# trinamic-controller-dribbler.net
KiCad netlist of a schematic drawn in Altium Designer
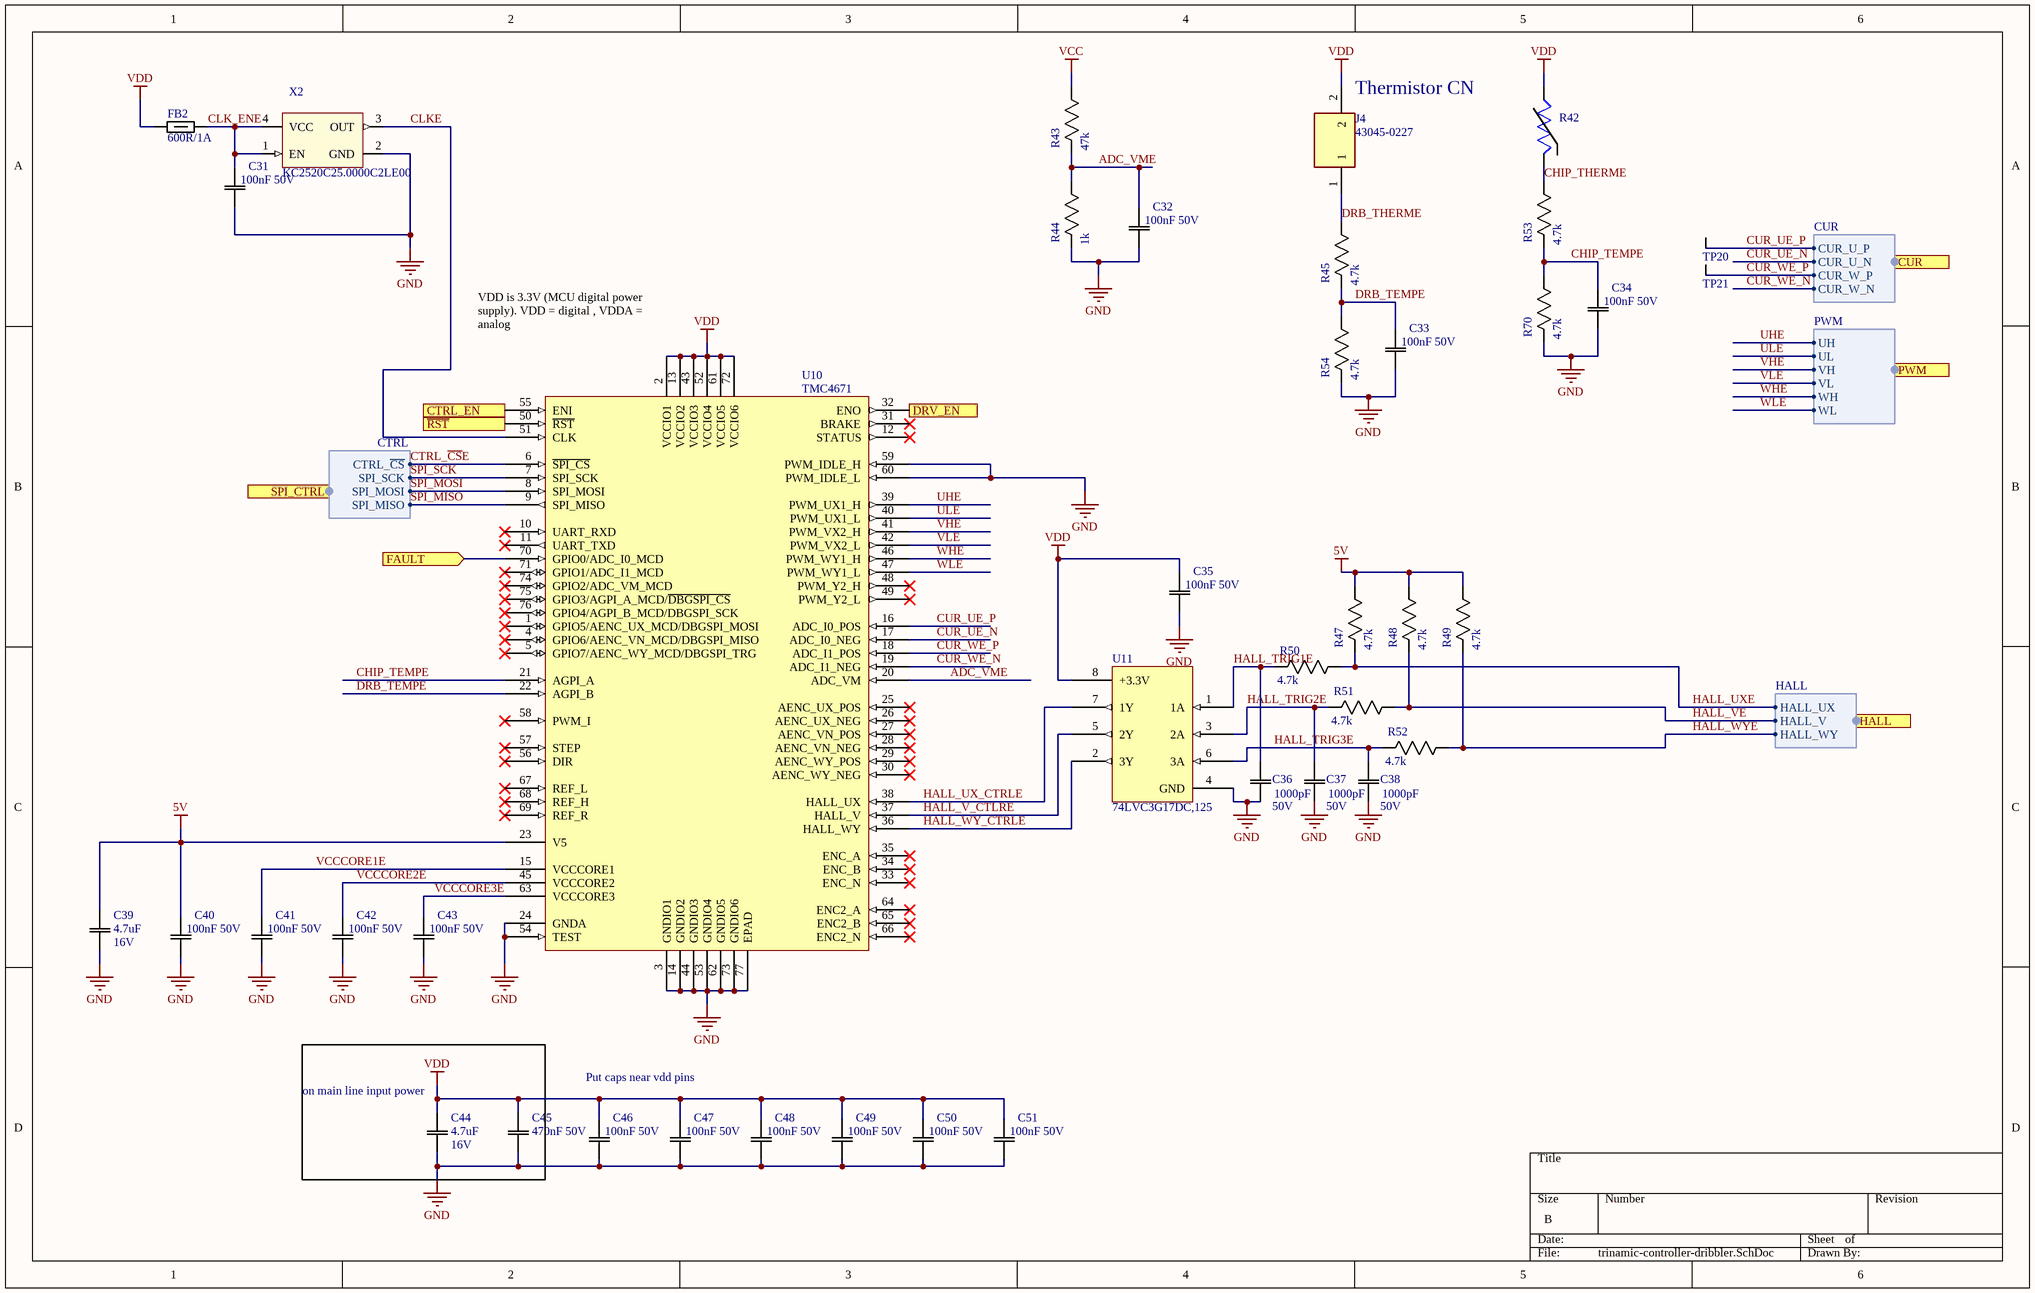
[diagram p0: trinamic-controller-dribbler.SchDoc]

(export (version "E")
  (design (tool "Eeschema 10.0.6"))
  (components
    (comp (ref "C31")
      (value "100nF 50V")
      (footprint "0603")
      (description "Default Symbol for Capacitors")
      (fields (field (name "TOLERANCE") "10%") (field (name "PART NUMBER") "CAP 100nF 50V"))
      (libsource (lib "capacitor_library") (part "CAP_Default"))
    )
    (comp (ref "C32")
      (value "100nF 50V")
      (footprint "0603")
      (description "Default Symbol for Capacitors")
      (fields (field (name "TOLERANCE") "10%") (field (name "PART NUMBER") "CAP 100nF 50V"))
      (libsource (lib "capacitor_library") (part "CAP_Default"))
    )
    (comp (ref "C33")
      (value "100nF 50V")
      (footprint "0603")
      (description "Default Symbol for Capacitors")
      (fields (field (name "TOLERANCE") "10%") (field (name "PART NUMBER") "CAP 100nF 50V"))
      (libsource (lib "capacitor_library") (part "CAP_Default"))
    )
    (comp (ref "C34")
      (value "100nF 50V")
      (footprint "0603")
      (description "Default Symbol for Capacitors")
      (fields (field (name "TOLERANCE") "10%") (field (name "PART NUMBER") "CAP 100nF 50V"))
      (libsource (lib "capacitor_library") (part "CAP_Default"))
    )
    (comp (ref "C35")
      (value "100nF 50V")
      (footprint "0603")
      (description "Default Symbol for Capacitors")
      (fields (field (name "TOLERANCE") "10%") (field (name "PART NUMBER") "CAP 100nF 50V"))
      (libsource (lib "capacitor_library") (part "CAP_Default"))
    )
    (comp (ref "C36")
      (value "1000pF")
      (footprint "0603")
      (description "Default Symbol for Capacitors")
      (fields
        (field (name "TOLERANCE") "10%")
        (field (name "RATING") "50V")
        (field (name "PART NUMBER") "CAP 1000pF 50V")
      )
      (libsource (lib "capacitor_library") (part "CAP_Default"))
    )
    (comp (ref "C37")
      (value "1000pF")
      (footprint "0603")
      (description "Default Symbol for Capacitors")
      (fields
        (field (name "TOLERANCE") "10%")
        (field (name "RATING") "50V")
        (field (name "PART NUMBER") "CAP 1000pF 50V")
      )
      (libsource (lib "capacitor_library") (part "CAP_Default"))
    )
    (comp (ref "C38")
      (value "1000pF")
      (footprint "0603")
      (description "Default Symbol for Capacitors")
      (fields
        (field (name "TOLERANCE") "10%")
        (field (name "RATING") "50V")
        (field (name "PART NUMBER") "CAP 1000pF 50V")
      )
      (libsource (lib "capacitor_library") (part "CAP_Default"))
    )
    (comp (ref "C39")
      (value "4.7uF")
      (footprint "0603")
      (description "Default Symbol for Capacitors")
      (fields
        (field (name "TOLERANCE") "10%")
        (field (name "RATING") "16V")
        (field (name "PART NUMBER") "CAP 4.7uF 16V")
      )
      (libsource (lib "capacitor_library") (part "CAP_Default"))
    )
    (comp (ref "C40")
      (value "100nF 50V")
      (footprint "0603")
      (description "Default Symbol for Capacitors")
      (fields (field (name "TOLERANCE") "10%") (field (name "PART NUMBER") "CAP 100nF 50V"))
      (libsource (lib "capacitor_library") (part "CAP_Default"))
    )
    (comp (ref "C41")
      (value "100nF 50V")
      (footprint "0603")
      (description "Default Symbol for Capacitors")
      (fields (field (name "TOLERANCE") "10%") (field (name "PART NUMBER") "CAP 100nF 50V"))
      (libsource (lib "capacitor_library") (part "CAP_Default"))
    )
    (comp (ref "C42")
      (value "100nF 50V")
      (footprint "0603")
      (description "Default Symbol for Capacitors")
      (fields (field (name "TOLERANCE") "10%") (field (name "PART NUMBER") "CAP 100nF 50V"))
      (libsource (lib "capacitor_library") (part "CAP_Default"))
    )
    (comp (ref "C43")
      (value "100nF 50V")
      (footprint "0603")
      (description "Default Symbol for Capacitors")
      (fields (field (name "TOLERANCE") "10%") (field (name "PART NUMBER") "CAP 100nF 50V"))
      (libsource (lib "capacitor_library") (part "CAP_Default"))
    )
    (comp (ref "C44")
      (value "4.7uF")
      (footprint "0603")
      (description "Default Symbol for Capacitors")
      (fields
        (field (name "TOLERANCE") "10%")
        (field (name "RATING") "16V")
        (field (name "PART NUMBER") "CAP 4.7uF 16V")
      )
      (libsource (lib "capacitor_library") (part "CAP_Default"))
    )
    (comp (ref "C45")
      (value "470nF 50V")
      (footprint "0603")
      (description "Default Symbol for Capacitors")
      (fields (field (name "TOLERANCE") "10%") (field (name "PART NUMBER") "CAP 470nF 50V"))
      (libsource (lib "capacitor_library") (part "CAP_Default"))
    )
    (comp (ref "C46")
      (value "100nF 50V")
      (footprint "0603")
      (description "Default Symbol for Capacitors")
      (fields (field (name "TOLERANCE") "10%") (field (name "PART NUMBER") "CAP 100nF 50V"))
      (libsource (lib "capacitor_library") (part "CAP_Default"))
    )
    (comp (ref "C47")
      (value "100nF 50V")
      (footprint "0603")
      (description "Default Symbol for Capacitors")
      (fields (field (name "TOLERANCE") "10%") (field (name "PART NUMBER") "CAP 100nF 50V"))
      (libsource (lib "capacitor_library") (part "CAP_Default"))
    )
    (comp (ref "C48")
      (value "100nF 50V")
      (footprint "0603")
      (description "Default Symbol for Capacitors")
      (fields (field (name "TOLERANCE") "10%") (field (name "PART NUMBER") "CAP 100nF 50V"))
      (libsource (lib "capacitor_library") (part "CAP_Default"))
    )
    (comp (ref "C49")
      (value "100nF 50V")
      (footprint "0603")
      (description "Default Symbol for Capacitors")
      (fields (field (name "TOLERANCE") "10%") (field (name "PART NUMBER") "CAP 100nF 50V"))
      (libsource (lib "capacitor_library") (part "CAP_Default"))
    )
    (comp (ref "C50")
      (value "100nF 50V")
      (footprint "0603")
      (description "Default Symbol for Capacitors")
      (fields (field (name "TOLERANCE") "10%") (field (name "PART NUMBER") "CAP 100nF 50V"))
      (libsource (lib "capacitor_library") (part "CAP_Default"))
    )
    (comp (ref "C51")
      (value "100nF 50V")
      (footprint "0603")
      (description "Default Symbol for Capacitors")
      (fields (field (name "TOLERANCE") "10%") (field (name "PART NUMBER") "CAP 100nF 50V"))
      (libsource (lib "capacitor_library") (part "CAP_Default"))
    )
    (comp (ref "FB2")
      (value "600R/1A")
      (footprint "0603")
      (fields (field (name "PART NUMBER") "FERRITE BEAD 200 MOHM 0603 1LN"))
      (libsource (lib "Inductor_Library") (part "FERRITE BEAD 200 MOHM 0603 1LN"))
    )
    (comp (ref "J4")
      (value "43045-0227")
      (footprint "MOLEX_0430450227")
      (description "Molex 43045-0227 2POS Microfit\r\ndual row, Vertical")
      (fields (field (name "PART NUMBER") "CN HDR 2POS Molex 43045-0227"))
      (libsource (lib "Connector_Library") (part "CN HDR 2POS Molex 43045-0227"))
    )
    (comp (ref "R42")
      (value "RES NTC 10k")
      (footprint "0603")
      (fields (field (name "PART NUMBER") "RES NTC 10k CHIP") (field (name "TOLERANCE") "1%"))
      (libsource (lib "Resistor_Library") (part "RES NTC 10k"))
    )
    (comp (ref "R43")
      (value "47k")
      (footprint "0603")
      (description "Default Resistor Symbol")
      (fields (field (name "TOLERANCE") "1%") (field (name "PART NUMBER") "RES 47k 1/8W - 1%"))
      (libsource (lib "") (part "RES_DEFAULT_2"))
    )
    (comp (ref "R44")
      (value "1k")
      (footprint "0603")
      (description "Default Resistor Symbol")
      (fields (field (name "TOLERANCE") "1%") (field (name "PART NUMBER") "RES 1k 1/8W - 1%"))
      (libsource (lib "") (part "RES_DEFAULT_1"))
    )
    (comp (ref "R45")
      (value "4.7k")
      (footprint "0603")
      (description "Default Resistor Symbol")
      (fields (field (name "TOLERANCE") "1%") (field (name "PART NUMBER") "RES 4.7k 1/8W - 1%"))
      (libsource (lib "") (part "RES_DEFAULT_1"))
    )
    (comp (ref "R47")
      (value "4.7k")
      (footprint "0603")
      (description "Default Resistor Symbol")
      (fields (field (name "TOLERANCE") "5%") (field (name "PART NUMBER") "RES 4.7k 1/8W - 5%"))
      (libsource (lib "Resistor_Library") (part "RES_DEFAULT"))
    )
    (comp (ref "R48")
      (value "4.7k")
      (footprint "0603")
      (description "Default Resistor Symbol")
      (fields (field (name "TOLERANCE") "5%") (field (name "PART NUMBER") "RES 4.7k 1/8W - 5%"))
      (libsource (lib "Resistor_Library") (part "RES_DEFAULT"))
    )
    (comp (ref "R49")
      (value "4.7k")
      (footprint "0603")
      (description "Default Resistor Symbol")
      (fields (field (name "TOLERANCE") "5%") (field (name "PART NUMBER") "RES 4.7k 1/8W - 5%"))
      (libsource (lib "") (part "RES_DEFAULT_1"))
    )
    (comp (ref "R50")
      (value "4.7k")
      (footprint "0603")
      (description "Default Resistor Symbol")
      (fields (field (name "TOLERANCE") "5%") (field (name "PART NUMBER") "RES 4.7k 1/8W - 5%"))
      (libsource (lib "Resistor_Library") (part "RES_DEFAULT"))
    )
    (comp (ref "R51")
      (value "4.7k")
      (footprint "0603")
      (description "Default Resistor Symbol")
      (fields (field (name "TOLERANCE") "5%") (field (name "PART NUMBER") "RES 4.7k 1/8W - 5%"))
      (libsource (lib "Resistor_Library") (part "RES_DEFAULT"))
    )
    (comp (ref "R52")
      (value "4.7k")
      (footprint "0603")
      (description "Default Resistor Symbol")
      (fields (field (name "TOLERANCE") "5%") (field (name "PART NUMBER") "RES 4.7k 1/8W - 5%"))
      (libsource (lib "Resistor_Library") (part "RES_DEFAULT"))
    )
    (comp (ref "R53")
      (value "4.7k")
      (footprint "0603")
      (description "Default Resistor Symbol")
      (fields (field (name "TOLERANCE") "1%") (field (name "PART NUMBER") "RES 4.7k 1/8W - 1%"))
      (libsource (lib "") (part "RES_DEFAULT_1"))
    )
    (comp (ref "R54")
      (value "4.7k")
      (footprint "0603")
      (description "Default Resistor Symbol")
      (fields (field (name "TOLERANCE") "1%") (field (name "PART NUMBER") "RES 4.7k 1/8W - 1%"))
      (libsource (lib "") (part "RES_DEFAULT_1"))
    )
    (comp (ref "R70")
      (value "4.7k")
      (footprint "0603")
      (description "Default Resistor Symbol")
      (fields (field (name "TOLERANCE") "1%") (field (name "PART NUMBER") "RES 4.7k 1/8W - 1%"))
      (libsource (lib "") (part "RES_DEFAULT_1"))
    )
    (comp (ref "TP20")
      (value "C_UE")
      (footprint "TP")
      (fields (field (name "PART NUMBER") "Test Point (Via)"))
      (libsource (lib "IC_Library") (part "Test Point (Via)"))
    )
    (comp (ref "TP21")
      (value "C_WE")
      (footprint "TP")
      (fields (field (name "PART NUMBER") "Test Point (Via)"))
      (libsource (lib "IC_Library") (part "Test Point (Via)"))
    )
    (comp (ref "U10")
      (value "TMC4671")
      (footprint "QFN40P1050X650X90_HS-77N")
      (description "Motor Driver, -40 To 125Deg C Rohs Compliant: Yes")
      (libsource (lib "IC_Library") (part "TMC4671"))
    )
    (comp (ref "U11")
      (value "74LVC3G17DC,125")
      (footprint "8-VSSOP")
      (description "IC BUFFER TRIPLE SCHMITT TRIGGER 5.5V VSSOP-8")
      (fields (field (name "PART NUMBER") "IC 74LVC3G17DC,125"))
      (libsource (lib "IC_Library") (part "IC 74LVC3G17DC,125"))
    )
    (comp (ref "X2")
      (value "KC2520C25.0000C2LE00")
      (footprint "KC2520C25.0000C2LE00")
      (description "Oscillator XO 25MHz ±15ppm 15pF CMOS 55% 2.5V/3.3V 4-Pin Mini-CSMD T/R")
      (fields (field (name "PART NUMBER") "XTAL OSC 25MHz 3.3V"))
      (libsource (lib "Oscillator_Library") (part "XTAL OSC 25MHz 3.3V"))
    )
  )
  (nets
    (net (code "5") (name "/ADC_VME") (class "Default")
      (node (ref "C32") (pin "2") (pinfunction "C2_2") (pintype "passive"))
      (node (ref "R43") (pin "2") (pinfunction "R2_2") (pintype "passive"))
      (node (ref "R44") (pin "1") (pinfunction "R1_1") (pintype "passive"))
      (node (ref "U10") (pin "20") (pinfunction "ADC_VM_20") (pintype "input"))
    )
    (net (code "6") (name "/CHIP_TEMPE") (class "Default")
      (node (ref "C34") (pin "2") (pinfunction "C2_2") (pintype "passive"))
      (node (ref "R53") (pin "2") (pinfunction "R2_2") (pintype "passive"))
      (node (ref "R70") (pin "1") (pinfunction "R1_1") (pintype "passive"))
      (node (ref "U10") (pin "21") (pinfunction "AGPI_A_21") (pintype "input"))
    )
    (net (code "7") (name "/CHIP_THERME") (class "Default")
      (node (ref "R42") (pin "1") (pinfunction "1_1") (pintype "passive"))
      (node (ref "R53") (pin "1") (pinfunction "R1_1") (pintype "passive"))
    )
    (net (code "8") (name "/CLKE") (class "Default")
      (node (ref "U10") (pin "51") (pinfunction "CLK_51") (pintype "input"))
      (node (ref "X2") (pin "3") (pinfunction "OUT_3") (pintype "output"))
    )
    (net (code "9") (name "/CLK_ENE") (class "Default")
      (node (ref "C31") (pin "2") (pinfunction "C2_2") (pintype "passive"))
      (node (ref "FB2") (pin "2") (pinfunction "2_2") (pintype "passive"))
      (node (ref "X2") (pin "1") (pinfunction "EN_1") (pintype "input"))
      (node (ref "X2") (pin "4") (pinfunction "VCC_4") (pintype "power_in"))
    )
    (net (code "10") (name "/CTRL_EN") (class "Default")
      (node (ref "U10") (pin "55") (pinfunction "ENI_55") (pintype "input"))
    )
    (net (code "11") (name "/CTRL_~{CS}E") (class "Default")
      (node (ref "U10") (pin "6") (pinfunction "~{SPI_CS}_6") (pintype "input"))
    )
    (net (code "12") (name "/CUR_UE_N") (class "Default")
      (node (ref "U10") (pin "17") (pinfunction "ADC_I0_NEG_17") (pintype "input"))
    )
    (net (code "13") (name "/CUR_UE_P") (class "Default")
      (node (ref "TP20") (pin "1") (pinfunction "1_1") (pintype "passive"))
      (node (ref "U10") (pin "16") (pinfunction "ADC_I0_POS_16") (pintype "input"))
    )
    (net (code "14") (name "/CUR_WE_N") (class "Default")
      (node (ref "U10") (pin "19") (pinfunction "ADC_I1_NEG_19") (pintype "input"))
    )
    (net (code "15") (name "/CUR_WE_P") (class "Default")
      (node (ref "TP21") (pin "1") (pinfunction "1_1") (pintype "passive"))
      (node (ref "U10") (pin "18") (pinfunction "ADC_I1_POS_18") (pintype "input"))
    )
    (net (code "16") (name "/DRB_TEMPE") (class "Default")
      (node (ref "C33") (pin "2") (pinfunction "C2_2") (pintype "passive"))
      (node (ref "R45") (pin "2") (pinfunction "R2_2") (pintype "passive"))
      (node (ref "R54") (pin "1") (pinfunction "R1_1") (pintype "passive"))
      (node (ref "U10") (pin "22") (pinfunction "AGPI_B_22") (pintype "input"))
    )
    (net (code "17") (name "/DRB_THERME") (class "Default")
      (node (ref "J4") (pin "1") (pinfunction "1_1") (pintype "passive"))
      (node (ref "R45") (pin "1") (pinfunction "R1_1") (pintype "passive"))
    )
    (net (code "18") (name "/DRV_EN") (class "Default")
      (node (ref "U10") (pin "32") (pinfunction "ENO_32") (pintype "output"))
    )
    (net (code "19") (name "/FAULT") (class "Default")
      (node (ref "U10") (pin "70") (pinfunction "GPIO0/ADC_I0_MCD_70") (pintype "input"))
    )
    (net (code "20") (name "/HALL_TRIG1E") (class "Default")
      (node (ref "C36") (pin "2") (pinfunction "C2_2") (pintype "passive"))
      (node (ref "R50") (pin "2") (pinfunction "R2_2") (pintype "passive"))
      (node (ref "U11") (pin "1") (pinfunction "1A_1") (pintype "input"))
    )
    (net (code "21") (name "/HALL_TRIG2E") (class "Default")
      (node (ref "C37") (pin "2") (pinfunction "C2_2") (pintype "passive"))
      (node (ref "R51") (pin "2") (pinfunction "R2_2") (pintype "passive"))
      (node (ref "U11") (pin "3") (pinfunction "2A_3") (pintype "input"))
    )
    (net (code "22") (name "/HALL_TRIG3E") (class "Default")
      (node (ref "C38") (pin "2") (pinfunction "C2_2") (pintype "passive"))
      (node (ref "R52") (pin "2") (pinfunction "R2_2") (pintype "passive"))
      (node (ref "U11") (pin "6") (pinfunction "3A_6") (pintype "input"))
    )
    (net (code "23") (name "/HALL_UXE") (class "Default")
      (node (ref "R47") (pin "2") (pinfunction "R2_2") (pintype "passive"))
      (node (ref "R50") (pin "1") (pinfunction "R1_1") (pintype "passive"))
    )
    (net (code "24") (name "/HALL_UX_CTRLE") (class "Default")
      (node (ref "U10") (pin "38") (pinfunction "HALL_UX_38") (pintype "input"))
      (node (ref "U11") (pin "7") (pinfunction "1Y_7") (pintype "output"))
    )
    (net (code "25") (name "/HALL_VE") (class "Default")
      (node (ref "R48") (pin "2") (pinfunction "R2_2") (pintype "passive"))
      (node (ref "R51") (pin "1") (pinfunction "R1_1") (pintype "passive"))
    )
    (net (code "26") (name "/HALL_V_CTLRE") (class "Default")
      (node (ref "U10") (pin "37") (pinfunction "HALL_V_37") (pintype "input"))
      (node (ref "U11") (pin "5") (pinfunction "2Y_5") (pintype "output"))
    )
    (net (code "27") (name "/HALL_WYE") (class "Default")
      (node (ref "R49") (pin "2") (pinfunction "R2_2") (pintype "passive"))
      (node (ref "R52") (pin "1") (pinfunction "R1_1") (pintype "passive"))
    )
    (net (code "28") (name "/HALL_WY_CTRLE") (class "Default")
      (node (ref "U10") (pin "36") (pinfunction "HALL_WY_36") (pintype "input"))
      (node (ref "U11") (pin "2") (pinfunction "3Y_2") (pintype "output"))
    )
    (net (code "29") (name "/SPI_MISO") (class "Default")
      (node (ref "U10") (pin "9") (pinfunction "SPI_MISO_9") (pintype "output"))
    )
    (net (code "30") (name "/SPI_MOSI") (class "Default")
      (node (ref "U10") (pin "8") (pinfunction "SPI_MOSI_8") (pintype "input"))
    )
    (net (code "31") (name "/SPI_SCK") (class "Default")
      (node (ref "U10") (pin "7") (pinfunction "SPI_SCK_7") (pintype "input"))
    )
    (net (code "32") (name "/UHE") (class "Default")
      (node (ref "U10") (pin "39") (pinfunction "PWM_UX1_H_39") (pintype "output"))
    )
    (net (code "33") (name "/ULE") (class "Default")
      (node (ref "U10") (pin "40") (pinfunction "PWM_UX1_L_40") (pintype "output"))
    )
    (net (code "34") (name "/VCCCORE1E") (class "Default")
      (node (ref "C41") (pin "2") (pinfunction "C2_2") (pintype "passive"))
      (node (ref "U10") (pin "15") (pinfunction "VCCCORE1_15") (pintype "power_in"))
    )
    (net (code "35") (name "/VCCCORE2E") (class "Default")
      (node (ref "C42") (pin "2") (pinfunction "C2_2") (pintype "passive"))
      (node (ref "U10") (pin "45") (pinfunction "VCCCORE2_45") (pintype "power_in"))
    )
    (net (code "36") (name "/VCCCORE3E") (class "Default")
      (node (ref "C43") (pin "2") (pinfunction "C2_2") (pintype "passive"))
      (node (ref "U10") (pin "63") (pinfunction "VCCCORE3_63") (pintype "power_in"))
    )
    (net (code "37") (name "/VHE") (class "Default")
      (node (ref "U10") (pin "41") (pinfunction "PWM_VX2_H_41") (pintype "output"))
    )
    (net (code "38") (name "/VLE") (class "Default")
      (node (ref "U10") (pin "42") (pinfunction "PWM_VX2_L_42") (pintype "output"))
    )
    (net (code "39") (name "/WHE") (class "Default")
      (node (ref "U10") (pin "46") (pinfunction "PWM_WY1_H_46") (pintype "output"))
    )
    (net (code "40") (name "/WLE") (class "Default")
      (node (ref "U10") (pin "47") (pinfunction "PWM_WY1_L_47") (pintype "output"))
    )
    (net (code "45") (name "/~{RST}") (class "Default")
      (node (ref "U10") (pin "50") (pinfunction "~{RST}_50") (pintype "input"))
    )
    (net (code "46") (name "5V") (class "Default")
      (node (ref "C39") (pin "2") (pinfunction "C2_2") (pintype "passive"))
      (node (ref "C40") (pin "2") (pinfunction "C2_2") (pintype "passive"))
      (node (ref "R47") (pin "1") (pinfunction "R1_1") (pintype "passive"))
      (node (ref "R48") (pin "1") (pinfunction "R1_1") (pintype "passive"))
      (node (ref "R49") (pin "1") (pinfunction "R1_1") (pintype "passive"))
      (node (ref "U10") (pin "23") (pinfunction "V5_23") (pintype "power_in"))
    )
    (net (code "47") (name "GND") (class "Default")
      (node (ref "C31") (pin "1") (pinfunction "C1_1") (pintype "passive"))
      (node (ref "C32") (pin "1") (pinfunction "C1_1") (pintype "passive"))
      (node (ref "C33") (pin "1") (pinfunction "C1_1") (pintype "passive"))
      (node (ref "C34") (pin "1") (pinfunction "C1_1") (pintype "passive"))
      (node (ref "C35") (pin "1") (pinfunction "C1_1") (pintype "passive"))
      (node (ref "C36") (pin "1") (pinfunction "C1_1") (pintype "passive"))
      (node (ref "C37") (pin "1") (pinfunction "C1_1") (pintype "passive"))
      (node (ref "C38") (pin "1") (pinfunction "C1_1") (pintype "passive"))
      (node (ref "C39") (pin "1") (pinfunction "C1_1") (pintype "passive"))
      (node (ref "C40") (pin "1") (pinfunction "C1_1") (pintype "passive"))
      (node (ref "C41") (pin "1") (pinfunction "C1_1") (pintype "passive"))
      (node (ref "C42") (pin "1") (pinfunction "C1_1") (pintype "passive"))
      (node (ref "C43") (pin "1") (pinfunction "C1_1") (pintype "passive"))
      (node (ref "C44") (pin "1") (pinfunction "C1_1") (pintype "passive"))
      (node (ref "C45") (pin "1") (pinfunction "C1_1") (pintype "passive"))
      (node (ref "C46") (pin "1") (pinfunction "C1_1") (pintype "passive"))
      (node (ref "C47") (pin "1") (pinfunction "C1_1") (pintype "passive"))
      (node (ref "C48") (pin "1") (pinfunction "C1_1") (pintype "passive"))
      (node (ref "C49") (pin "1") (pinfunction "C1_1") (pintype "passive"))
      (node (ref "C50") (pin "1") (pinfunction "C1_1") (pintype "passive"))
      (node (ref "C51") (pin "1") (pinfunction "C1_1") (pintype "passive"))
      (node (ref "R44") (pin "2") (pinfunction "R2_2") (pintype "passive"))
      (node (ref "R54") (pin "2") (pinfunction "R2_2") (pintype "passive"))
      (node (ref "R70") (pin "2") (pinfunction "R2_2") (pintype "passive"))
      (node (ref "U10") (pin "14") (pinfunction "GNDIO2_14") (pintype "power_in"))
      (node (ref "U10") (pin "24") (pinfunction "GNDA_24") (pintype "power_in"))
      (node (ref "U10") (pin "3") (pinfunction "GNDIO1_3") (pintype "power_in"))
      (node (ref "U10") (pin "44") (pinfunction "GNDIO3_44") (pintype "power_in"))
      (node (ref "U10") (pin "53") (pinfunction "GNDIO4_53") (pintype "power_in"))
      (node (ref "U10") (pin "54") (pinfunction "TEST_54") (pintype "input"))
      (node (ref "U10") (pin "59") (pinfunction "PWM_IDLE_H_59") (pintype "input"))
      (node (ref "U10") (pin "60") (pinfunction "PWM_IDLE_L_60") (pintype "input"))
      (node (ref "U10") (pin "62") (pinfunction "GNDIO5_62") (pintype "power_in"))
      (node (ref "U10") (pin "73") (pinfunction "GNDIO6_73") (pintype "power_in"))
      (node (ref "U10") (pin "77") (pinfunction "EPAD_77") (pintype "passive"))
      (node (ref "U11") (pin "4") (pinfunction "GND_4") (pintype "power_in"))
      (node (ref "X2") (pin "2") (pinfunction "GND_2") (pintype "power_in"))
    )
    (net (code "48") (name "VCC") (class "Default")
      (node (ref "R43") (pin "1") (pinfunction "R1_1") (pintype "passive"))
    )
    (net (code "49") (name "VDD") (class "Default")
      (node (ref "C35") (pin "2") (pinfunction "C2_2") (pintype "passive"))
      (node (ref "C44") (pin "2") (pinfunction "C2_2") (pintype "passive"))
      (node (ref "C45") (pin "2") (pinfunction "C2_2") (pintype "passive"))
      (node (ref "C46") (pin "2") (pinfunction "C2_2") (pintype "passive"))
      (node (ref "C47") (pin "2") (pinfunction "C2_2") (pintype "passive"))
      (node (ref "C48") (pin "2") (pinfunction "C2_2") (pintype "passive"))
      (node (ref "C49") (pin "2") (pinfunction "C2_2") (pintype "passive"))
      (node (ref "C50") (pin "2") (pinfunction "C2_2") (pintype "passive"))
      (node (ref "C51") (pin "2") (pinfunction "C2_2") (pintype "passive"))
      (node (ref "FB2") (pin "1") (pinfunction "1_1") (pintype "passive"))
      (node (ref "J4") (pin "2") (pinfunction "2_2") (pintype "passive"))
      (node (ref "R42") (pin "2") (pinfunction "2_2") (pintype "passive"))
      (node (ref "U10") (pin "13") (pinfunction "VCCIO2_13") (pintype "power_in"))
      (node (ref "U10") (pin "2") (pinfunction "VCCIO1_2") (pintype "power_in"))
      (node (ref "U10") (pin "43") (pinfunction "VCCIO3_43") (pintype "power_in"))
      (node (ref "U10") (pin "52") (pinfunction "VCCIO4_52") (pintype "power_in"))
      (node (ref "U10") (pin "61") (pinfunction "VCCIO5_61") (pintype "power_in"))
      (node (ref "U10") (pin "72") (pinfunction "VCCIO6_72") (pintype "power_in"))
      (node (ref "U11") (pin "8") (pinfunction "+3.3V_8") (pintype "power_in"))
    )
    (net (code "50") (name "unconnected-(U10-AENC_UX_NEG-Pad26)") (class "Default")
      (node (ref "U10") (pin "26") (pinfunction "AENC_UX_NEG_26") (pintype "input+no_connect"))
    )
    (net (code "51") (name "unconnected-(U10-AENC_UX_POS-Pad25)") (class "Default")
      (node (ref "U10") (pin "25") (pinfunction "AENC_UX_POS_25") (pintype "input+no_connect"))
    )
    (net (code "52") (name "unconnected-(U10-AENC_VN_NEG-Pad28)") (class "Default")
      (node (ref "U10") (pin "28") (pinfunction "AENC_VN_NEG_28") (pintype "input+no_connect"))
    )
    (net (code "53") (name "unconnected-(U10-AENC_VN_POS-Pad27)") (class "Default")
      (node (ref "U10") (pin "27") (pinfunction "AENC_VN_POS_27") (pintype "input+no_connect"))
    )
    (net (code "54") (name "unconnected-(U10-AENC_WY_NEG-Pad30)") (class "Default")
      (node (ref "U10") (pin "30") (pinfunction "AENC_WY_NEG_30") (pintype "input+no_connect"))
    )
    (net (code "55") (name "unconnected-(U10-AENC_WY_POS-Pad29)") (class "Default")
      (node (ref "U10") (pin "29") (pinfunction "AENC_WY_POS_29") (pintype "input+no_connect"))
    )
    (net (code "56") (name "unconnected-(U10-BRAKE-Pad31)") (class "Default")
      (node (ref "U10") (pin "31") (pinfunction "BRAKE_31") (pintype "output+no_connect"))
    )
    (net (code "57") (name "unconnected-(U10-DIR-Pad56)") (class "Default")
      (node (ref "U10") (pin "56") (pinfunction "DIR_56") (pintype "input+no_connect"))
    )
    (net (code "58") (name "unconnected-(U10-ENC2_A-Pad64)") (class "Default")
      (node (ref "U10") (pin "64") (pinfunction "ENC2_A_64") (pintype "input+no_connect"))
    )
    (net (code "59") (name "unconnected-(U10-ENC2_B-Pad65)") (class "Default")
      (node (ref "U10") (pin "65") (pinfunction "ENC2_B_65") (pintype "input+no_connect"))
    )
    (net (code "60") (name "unconnected-(U10-ENC2_N-Pad66)") (class "Default")
      (node (ref "U10") (pin "66") (pinfunction "ENC2_N_66") (pintype "input+no_connect"))
    )
    (net (code "61") (name "unconnected-(U10-ENC_A-Pad35)") (class "Default")
      (node (ref "U10") (pin "35") (pinfunction "ENC_A_35") (pintype "input+no_connect"))
    )
    (net (code "62") (name "unconnected-(U10-ENC_B-Pad34)") (class "Default")
      (node (ref "U10") (pin "34") (pinfunction "ENC_B_34") (pintype "input+no_connect"))
    )
    (net (code "63") (name "unconnected-(U10-ENC_N-Pad33)") (class "Default")
      (node (ref "U10") (pin "33") (pinfunction "ENC_N_33") (pintype "input+no_connect"))
    )
    (net (code "64") (name "unconnected-(U10-GPIO1{slash}ADC_I1_MCD-Pad71)") (class "Default")
      (node (ref "U10") (pin "71") (pinfunction "GPIO1/ADC_I1_MCD_71") (pintype "bidirectional+no_connect"))
    )
    (net (code "65") (name "unconnected-(U10-GPIO2{slash}ADC_VM_MCD-Pad74)") (class "Default")
      (node (ref "U10") (pin "74") (pinfunction "GPIO2/ADC_VM_MCD_74") (pintype "bidirectional+no_connect"))
    )
    (net (code "66") (name "unconnected-(U10-GPIO3{slash}AGPI_A_MCD{slash}~{DBGSPI_CS}-Pad75)") (class "Default")
      (node (ref "U10") (pin "75") (pinfunction "GPIO3/AGPI_A_MCD/~{DBGSPI_CS}_75") (pintype "bidirectional+no_connect"))
    )
    (net (code "67") (name "unconnected-(U10-GPIO4{slash}AGPI_B_MCD{slash}DBGSPI_SCK-Pad76)") (class "Default")
      (node (ref "U10") (pin "76") (pinfunction "GPIO4/AGPI_B_MCD/DBGSPI_SCK_76") (pintype "bidirectional+no_connect"))
    )
    (net (code "68") (name "unconnected-(U10-GPIO5{slash}AENC_UX_MCD{slash}DBGSPI_MOSI-Pad1)") (class "Default")
      (node (ref "U10") (pin "1") (pinfunction "GPIO5/AENC_UX_MCD/DBGSPI_MOSI_1") (pintype "bidirectional+no_connect"))
    )
    (net (code "69") (name "unconnected-(U10-GPIO6{slash}AENC_VN_MCD{slash}DBGSPI_MISO-Pad4)") (class "Default")
      (node (ref "U10") (pin "4") (pinfunction "GPIO6/AENC_VN_MCD/DBGSPI_MISO_4") (pintype "bidirectional+no_connect"))
    )
    (net (code "70") (name "unconnected-(U10-GPIO7{slash}AENC_WY_MCD{slash}DBGSPI_TRG-Pad5)") (class "Default")
      (node (ref "U10") (pin "5") (pinfunction "GPIO7/AENC_WY_MCD/DBGSPI_TRG_5") (pintype "bidirectional+no_connect"))
    )
    (net (code "71") (name "unconnected-(U10-PWM_I-Pad58)") (class "Default")
      (node (ref "U10") (pin "58") (pinfunction "PWM_I_58") (pintype "input+no_connect"))
    )
    (net (code "72") (name "unconnected-(U10-PWM_Y2_H-Pad48)") (class "Default")
      (node (ref "U10") (pin "48") (pinfunction "PWM_Y2_H_48") (pintype "output+no_connect"))
    )
    (net (code "73") (name "unconnected-(U10-PWM_Y2_L-Pad49)") (class "Default")
      (node (ref "U10") (pin "49") (pinfunction "PWM_Y2_L_49") (pintype "output+no_connect"))
    )
    (net (code "74") (name "unconnected-(U10-REF_H-Pad68)") (class "Default")
      (node (ref "U10") (pin "68") (pinfunction "REF_H_68") (pintype "input+no_connect"))
    )
    (net (code "75") (name "unconnected-(U10-REF_L-Pad67)") (class "Default")
      (node (ref "U10") (pin "67") (pinfunction "REF_L_67") (pintype "input+no_connect"))
    )
    (net (code "76") (name "unconnected-(U10-REF_R-Pad69)") (class "Default")
      (node (ref "U10") (pin "69") (pinfunction "REF_R_69") (pintype "input+no_connect"))
    )
    (net (code "77") (name "unconnected-(U10-STATUS-Pad12)") (class "Default")
      (node (ref "U10") (pin "12") (pinfunction "STATUS_12") (pintype "output+no_connect"))
    )
    (net (code "78") (name "unconnected-(U10-STEP-Pad57)") (class "Default")
      (node (ref "U10") (pin "57") (pinfunction "STEP_57") (pintype "input+no_connect"))
    )
    (net (code "79") (name "unconnected-(U10-UART_RXD-Pad10)") (class "Default")
      (node (ref "U10") (pin "10") (pinfunction "UART_RXD_10") (pintype "input+no_connect"))
    )
    (net (code "80") (name "unconnected-(U10-UART_TXD-Pad11)") (class "Default")
      (node (ref "U10") (pin "11") (pinfunction "UART_TXD_11") (pintype "output+no_connect"))
    )
  )
)
